# Encoder_PCB.net
KiCad netlist of a schematic drawn in Altium Designer
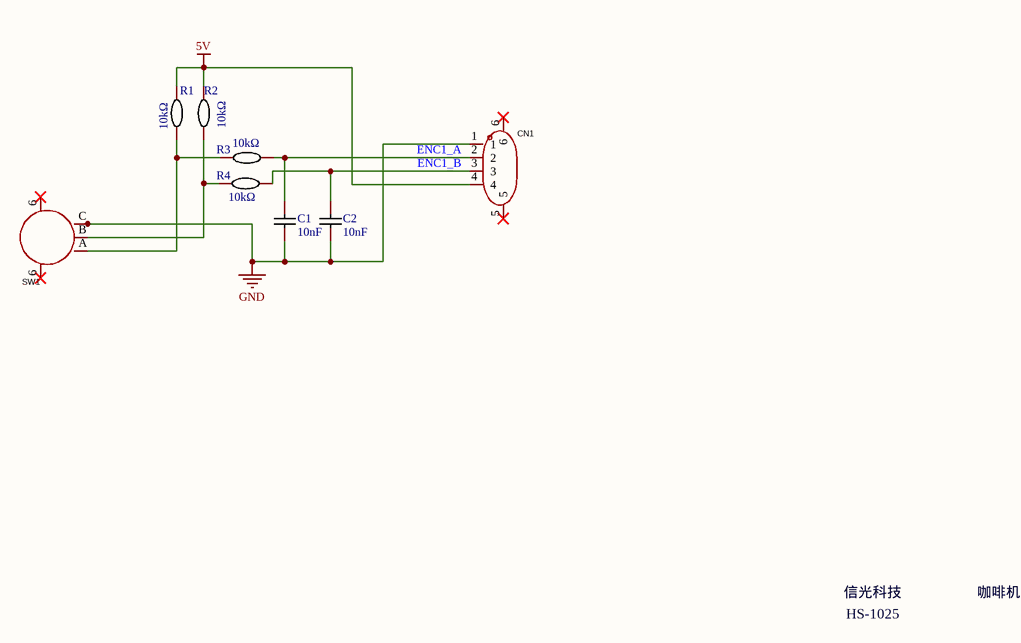
[diagram p0: Encoder_PCB.SchDoc]

(export (version "E")
  (design (tool "Eeschema 10.0.6"))
  (components
    (comp (ref "C1")
      (value "CC0603KRX7R9BB103")
      (footprint "C0603")
      (fields
        (field (name "NAME") "10nF")
        (field (name "MANUFACTURER") "YAGEO(国巨)")
        (field (name "TOLERANCE") "±10%")
      )
      (libsource (lib "PCB_Project") (part "CC0603KRX7R9BB103"))
    )
    (comp (ref "C2")
      (value "CC0603KRX7R9BB103")
      (footprint "C0603")
      (fields
        (field (name "NAME") "10nF")
        (field (name "MANUFACTURER") "YAGEO(国巨)")
        (field (name "TOLERANCE") "±10%")
      )
      (libsource (lib "PCB_Project") (part "CC0603KRX7R9BB103"))
    )
    (comp (ref "CN1")
      (value "WAFER-GH1.25-4PLB")
      (footprint "CONN-SMD_4P-P1.25_XUNPU_WAFER-GH1.25-4PLB")
      (fields (field (name "MANUFACTURER") "XUNPU(讯普)"))
      (libsource (lib "PCB_Project") (part "WAFER-GH1.25-4PLB"))
    )
    (comp (ref "R1")
      (value "10kΩ")
      (footprint "R0603")
      (fields
        (field (name "MANUFACTURER") "UNI-ROYAL(厚声)")
        (field (name "MANUFACTURER PART") "0603WAF1002T5E")
      )
      (libsource (lib "PCB_Project") (part "0603WAF1002T5E"))
    )
    (comp (ref "R2")
      (value "10kΩ")
      (footprint "R0603")
      (fields
        (field (name "MANUFACTURER") "UNI-ROYAL(厚声)")
        (field (name "MANUFACTURER PART") "0603WAF1002T5E")
      )
      (libsource (lib "PCB_Project") (part "0603WAF1002T5E"))
    )
    (comp (ref "R3")
      (value "10kΩ")
      (footprint "R0603")
      (fields
        (field (name "MANUFACTURER") "UNI-ROYAL(厚声)")
        (field (name "MANUFACTURER PART") "0603WAF1002T5E")
      )
      (libsource (lib "PCB_Project") (part "0603WAF1002T5E"))
    )
    (comp (ref "R4")
      (value "10kΩ")
      (footprint "R0603")
      (fields
        (field (name "MANUFACTURER") "UNI-ROYAL(厚声)")
        (field (name "MANUFACTURER PART") "0603WAF1002T5E")
      )
      (libsource (lib "PCB_Project") (part "0603WAF1002T5E"))
    )
    (comp (ref "SW1")
      (value "PEC16-4120F-N0012")
      (footprint "SW-SMD_PEC16-4120F-N0012")
      (fields (field (name "MANUFACTURER") "BOURNS"))
      (libsource (lib "PCB_Project") (part "PEC16-4120F-N0012"))
    )
  )
  (nets
    (net (code "1") (name "/ENC1_A") (class "Default")
      (node (ref "C1") (pin "2") (pinfunction "2_2") (pintype "passive"))
      (node (ref "CN1") (pin "2") (pinfunction "2_2") (pintype "passive"))
      (node (ref "R3") (pin "1") (pinfunction "1_1") (pintype "passive"))
    )
    (net (code "2") (name "/ENC1_B") (class "Default")
      (node (ref "C2") (pin "2") (pinfunction "2_2") (pintype "passive"))
      (node (ref "CN1") (pin "3") (pinfunction "3_3") (pintype "passive"))
      (node (ref "R4") (pin "1") (pinfunction "1_1") (pintype "passive"))
    )
    (net (code "3") (name "5V") (class "Default")
      (node (ref "CN1") (pin "4") (pinfunction "4_4") (pintype "passive"))
      (node (ref "R1") (pin "1") (pinfunction "1_1") (pintype "passive"))
      (node (ref "R2") (pin "1") (pinfunction "1_1") (pintype "passive"))
    )
    (net (code "4") (name "GND") (class "Default")
      (node (ref "C1") (pin "1") (pinfunction "1_1") (pintype "passive"))
      (node (ref "C2") (pin "1") (pinfunction "1_1") (pintype "passive"))
      (node (ref "CN1") (pin "1") (pinfunction "1_1") (pintype "passive"))
      (node (ref "SW1") (pin "C") (pinfunction "C_C") (pintype "passive"))
    )
    (net (code "5") (name "Net-(R1-Pad2)") (class "Default")
      (node (ref "R1") (pin "2") (pinfunction "2_2") (pintype "passive"))
      (node (ref "R3") (pin "2") (pinfunction "2_2") (pintype "passive"))
      (node (ref "SW1") (pin "A") (pinfunction "A_A") (pintype "passive"))
    )
    (net (code "6") (name "Net-(R2-Pad2)") (class "Default")
      (node (ref "R2") (pin "2") (pinfunction "2_2") (pintype "passive"))
      (node (ref "R4") (pin "2") (pinfunction "2_2") (pintype "passive"))
      (node (ref "SW1") (pin "B") (pinfunction "B_B") (pintype "passive"))
    )
    (net (code "7") (name "unconnected-(CN1-Pad5)") (class "Default")
      (node (ref "CN1") (pin "5") (pinfunction "5_5") (pintype "passive+no_connect"))
    )
    (net (code "8") (name "unconnected-(CN1-Pad6)") (class "Default")
      (node (ref "CN1") (pin "6") (pinfunction "6_6") (pintype "passive+no_connect"))
    )
    (net (code "9") (name "unconnected-(SW1-Pad6)") (class "Default")
      (node (ref "SW1") (pin "6") (pinfunction "6_6") (pintype "passive+no_connect"))
    )
    (net (code "10") (name "unconnected-(SW1-Pad6)_1") (class "Default")
      (node (ref "SW1") (pin "6") (pinfunction "6_6") (pintype "passive+no_connect"))
    )
  )
)
